# Vectr_1_3.net
KiCad netlist of a schematic drawn in EAGLE
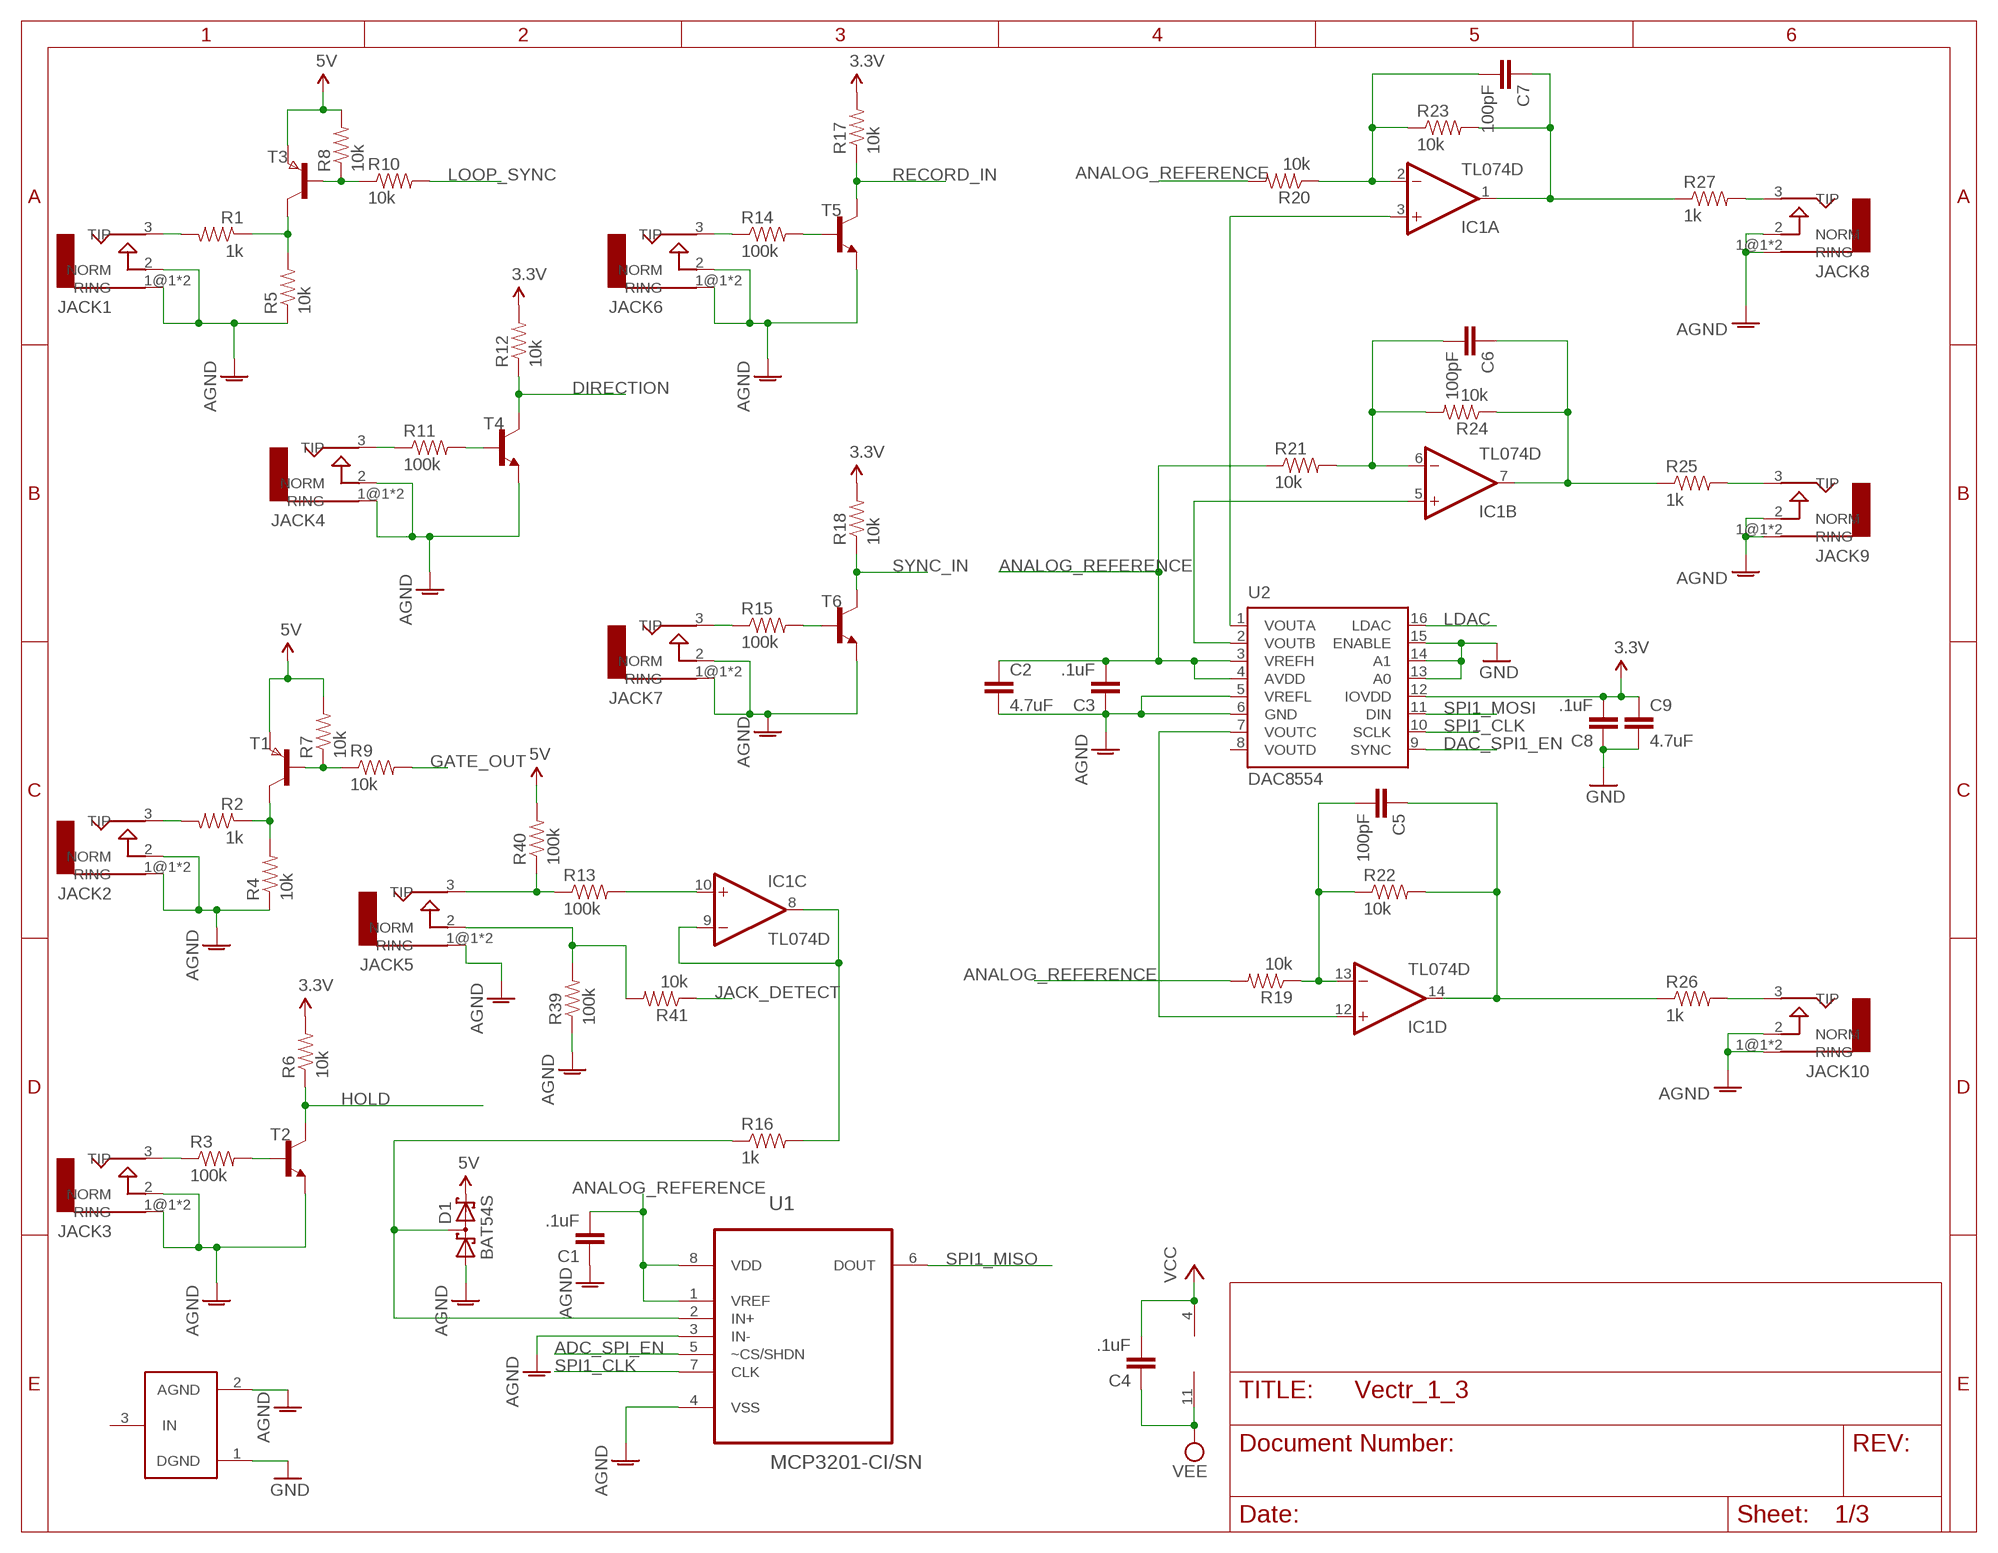
[diagram p0: schematic, sheet 1]
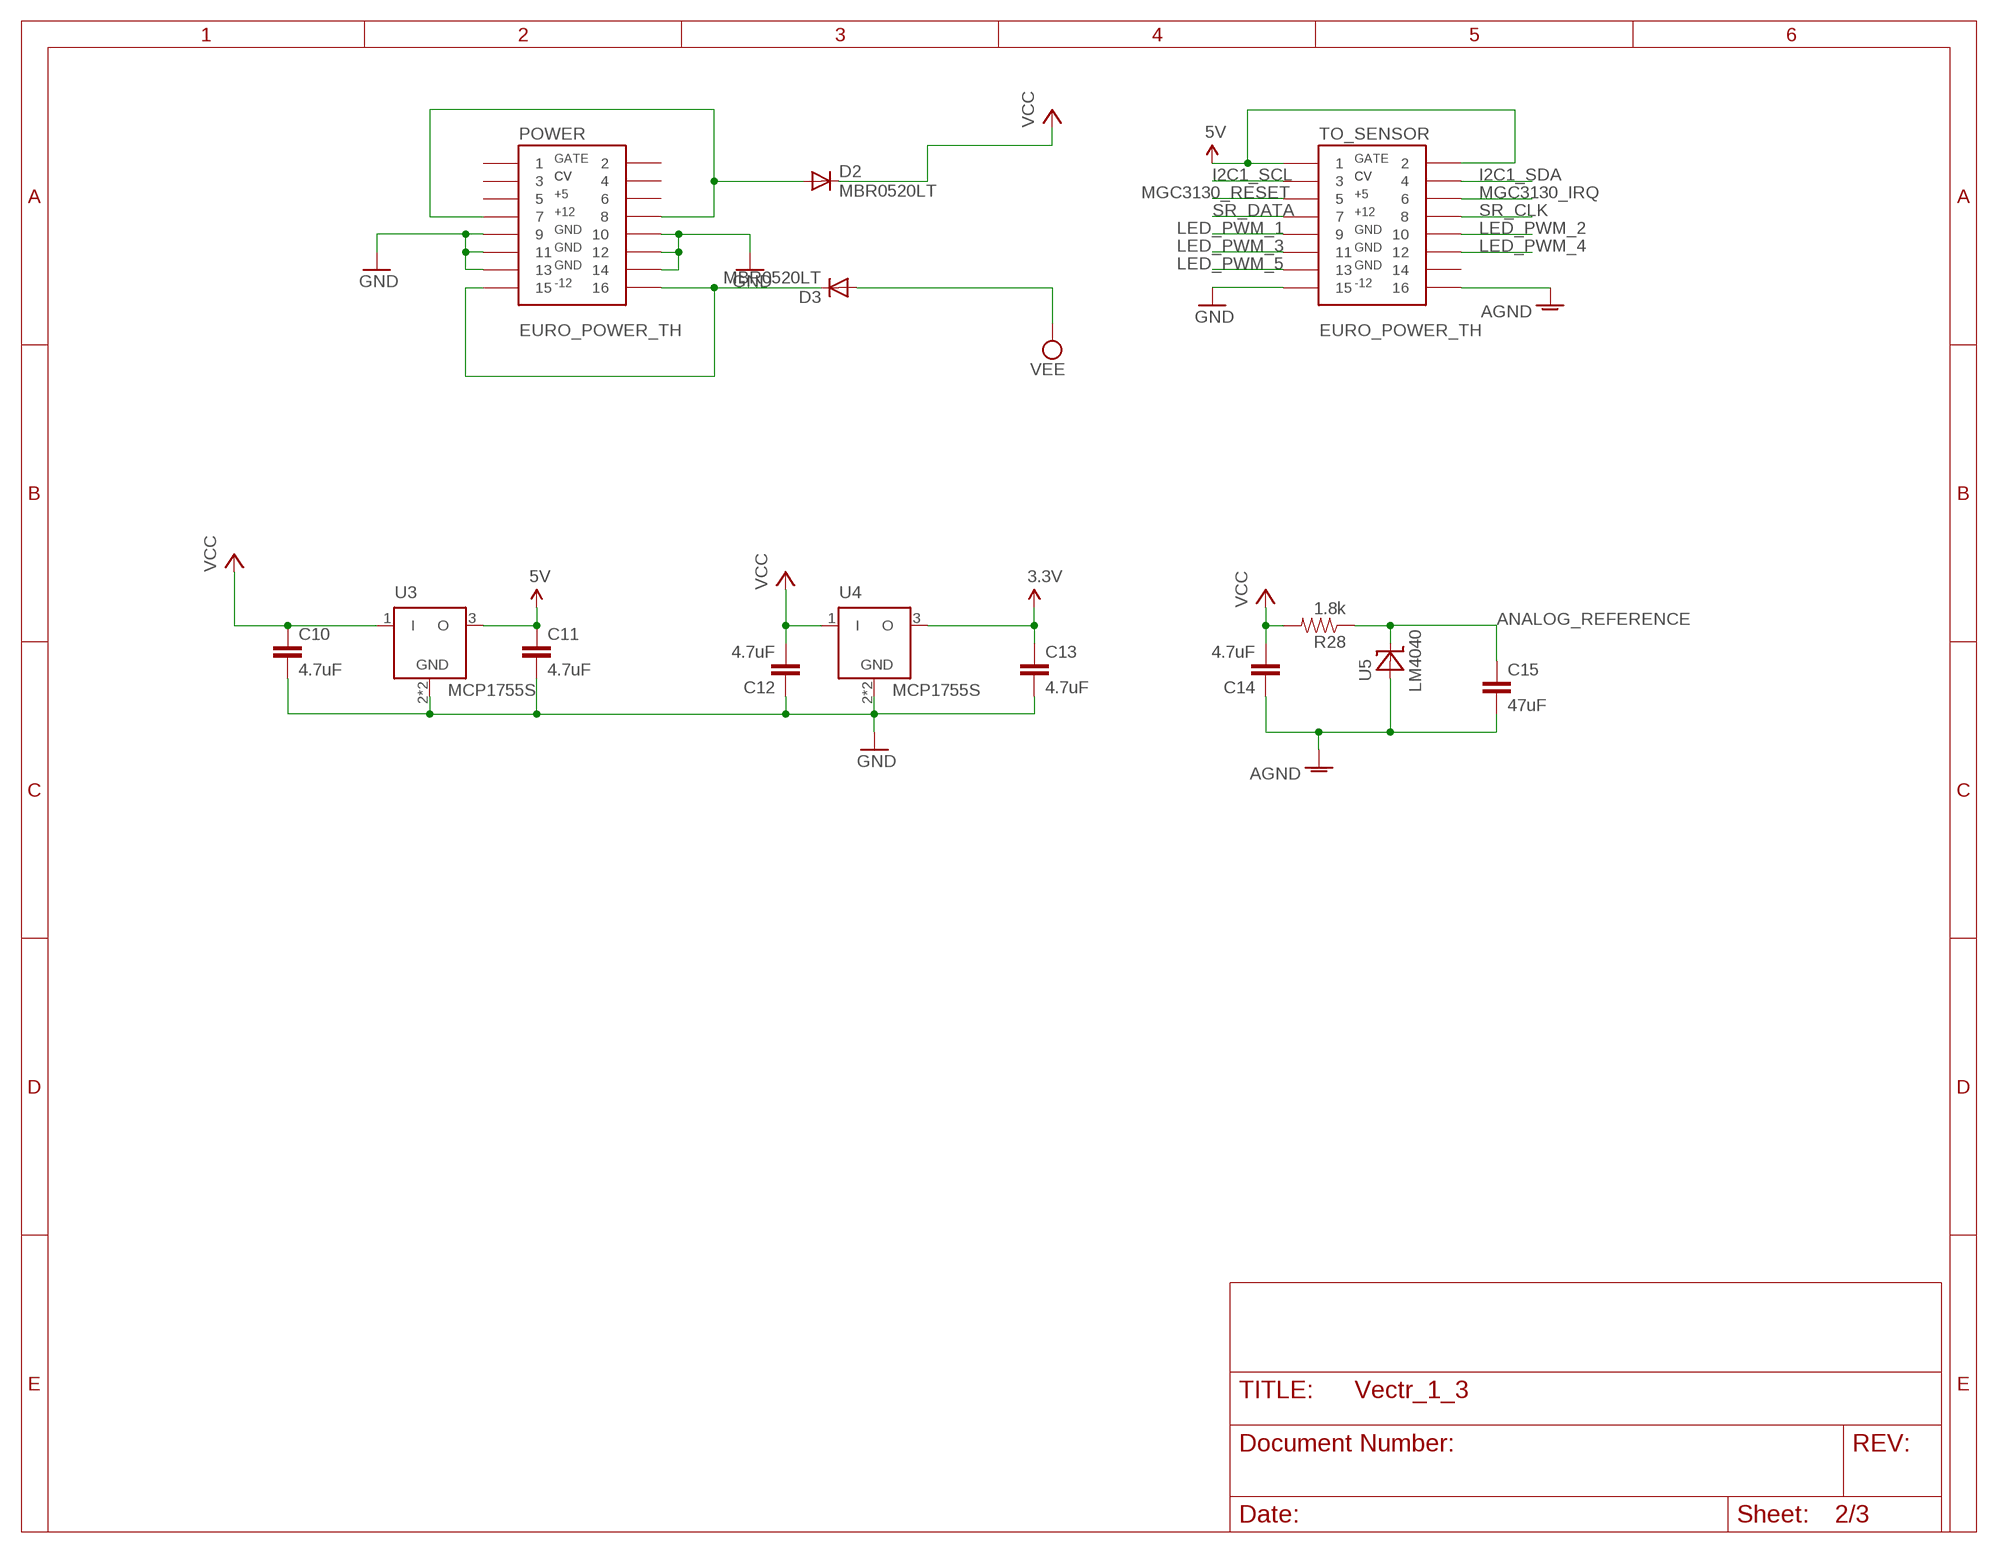
[diagram p1: schematic, sheet 2]
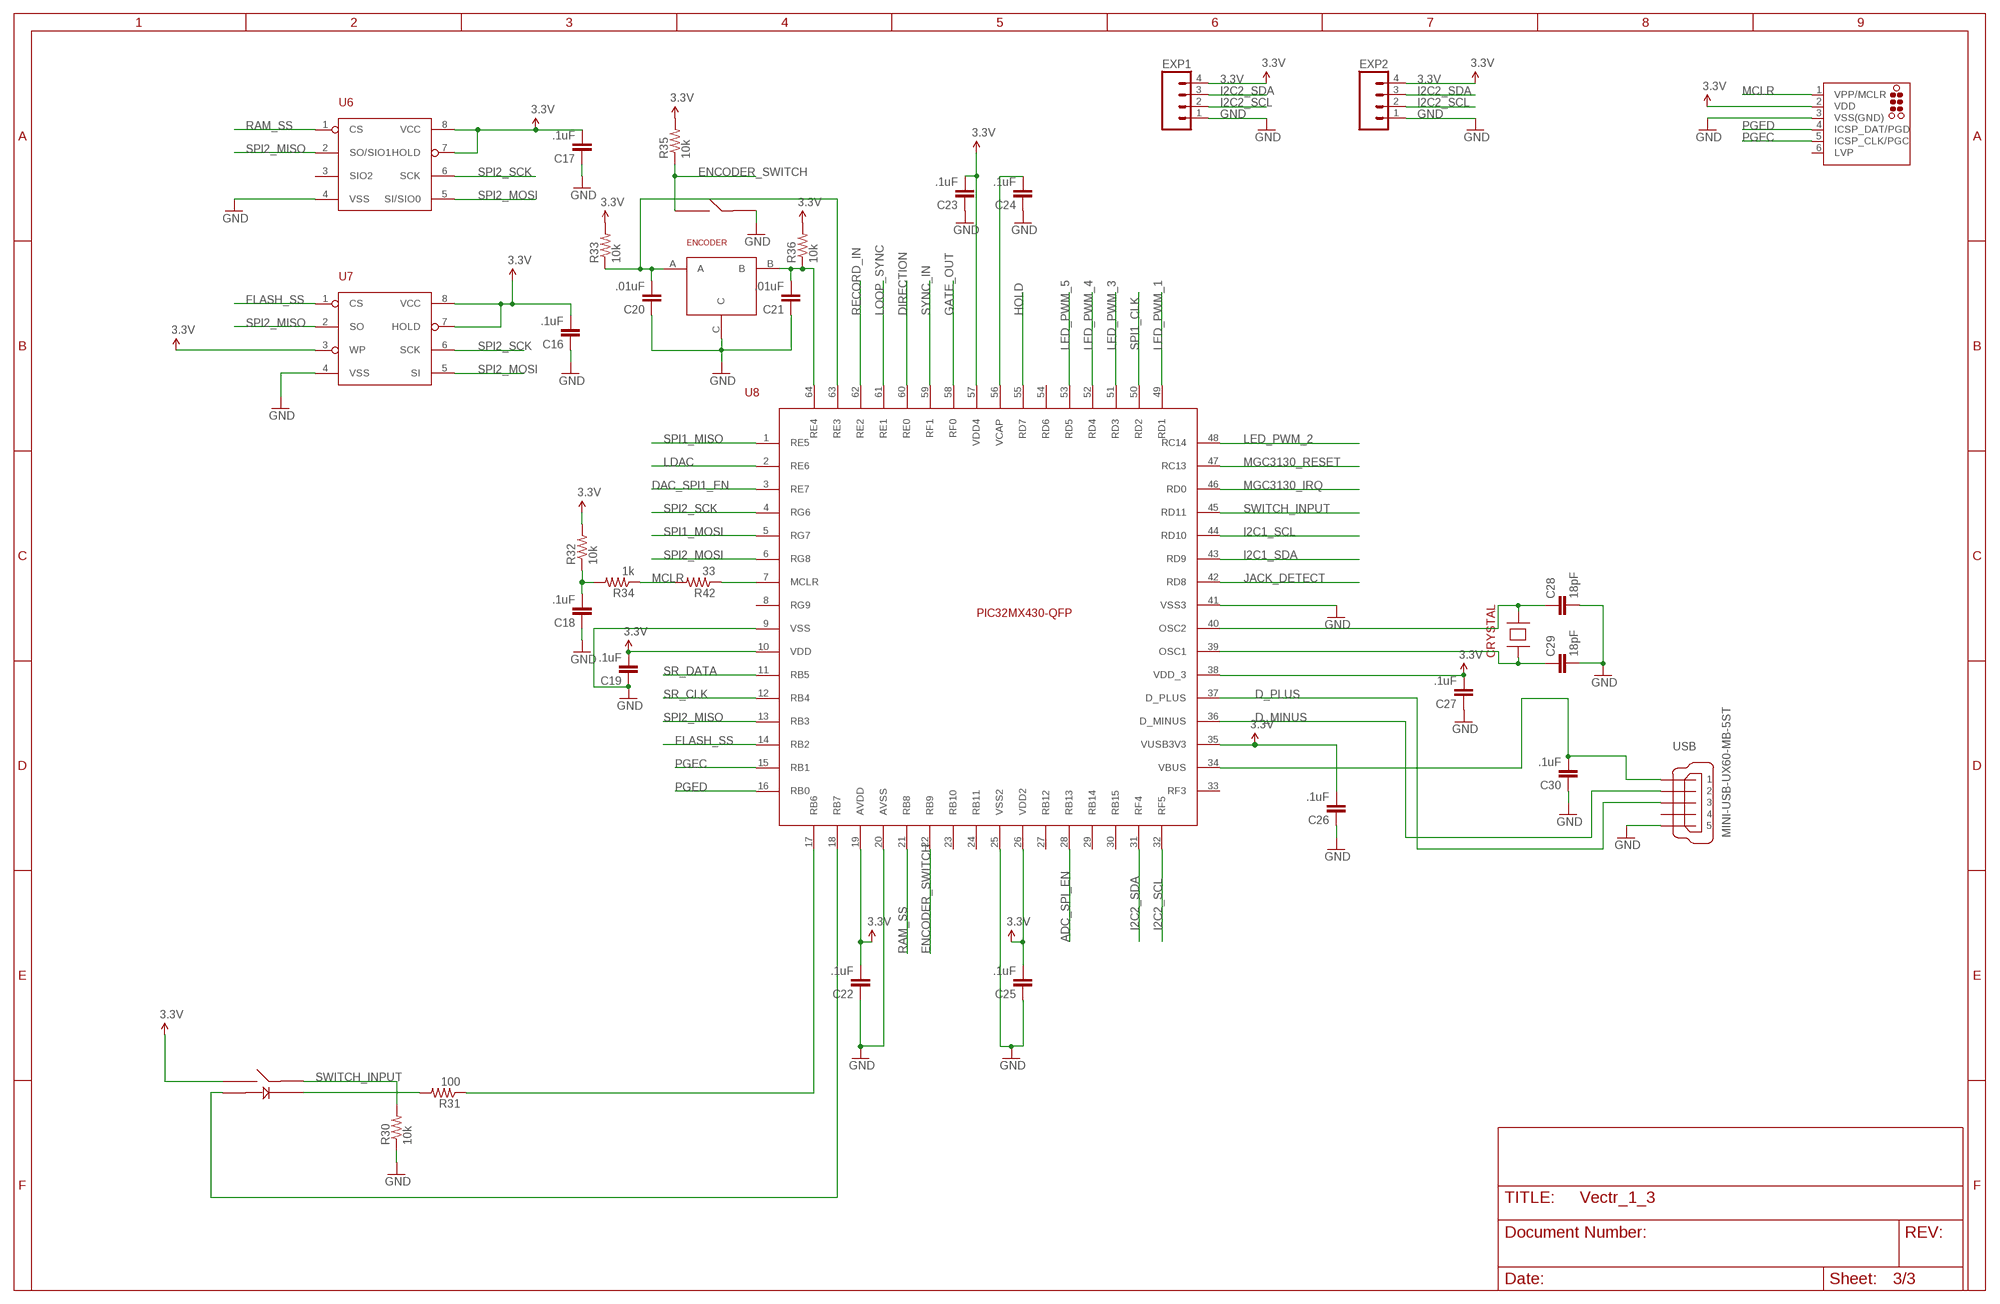
[diagram p2: schematic, sheet 3]

(export (version "E")
  (design (tool "Eeschema 10.0.6"))
  (components
    (comp (ref "C1")
      (value ".1uF")
      (footprint "eagle-import:0402-CAP")
      (libsource (lib "eagle-import") (part "SparkFun-Passives_CAP0402-CAP"))
    )
    (comp (ref "C2")
      (value "4.7uF")
      (footprint "eagle-import:0805")
      (libsource (lib "eagle-import") (part "CAP0805"))
    )
    (comp (ref "C3")
      (value ".1uF")
      (footprint "eagle-import:0402-CAP")
      (libsource (lib "eagle-import") (part "SparkFun-Passives_CAP0402-CAP"))
    )
    (comp (ref "C4")
      (value ".1uF")
      (footprint "eagle-import:0402-CAP")
      (libsource (lib "eagle-import") (part "SparkFun-Passives_CAP0402-CAP"))
    )
    (comp (ref "C5")
      (value "100pF")
      (footprint "eagle-import:0402-CAP")
      (libsource (lib "eagle-import") (part "SparkFun-Passives_CAP0402-CAP"))
    )
    (comp (ref "C6")
      (value "100pF")
      (footprint "eagle-import:0402-CAP")
      (libsource (lib "eagle-import") (part "SparkFun-Passives_CAP0402-CAP"))
    )
    (comp (ref "C7")
      (value "100pF")
      (footprint "eagle-import:0402-CAP")
      (libsource (lib "eagle-import") (part "SparkFun-Passives_CAP0402-CAP"))
    )
    (comp (ref "C8")
      (value ".1uF")
      (footprint "eagle-import:0402-CAP")
      (libsource (lib "eagle-import") (part "SparkFun-Passives_CAP0402-CAP"))
    )
    (comp (ref "C9")
      (value "4.7uF")
      (footprint "eagle-import:0805")
      (libsource (lib "eagle-import") (part "CAP0805"))
    )
    (comp (ref "D1")
      (value "BAT54S")
      (footprint "eagle-import:SOT23")
      (libsource (lib "eagle-import") (part "BAT54S"))
    )
    (comp (ref "GND_CONNECT")
      (value "GND_CONNECT")
      (footprint "eagle-import:GND_CONNECT")
      (libsource (lib "eagle-import") (part "GND_CONNECT"))
    )
    (comp (ref "IC1")
      (value "TL074D")
      (footprint "eagle-import:SO14")
      (libsource (lib "eagle-import") (part "TL074D"))
    )
    (comp (ref "JACK1")
      (value "AUDIO-JACKERTHENVAR")
      (footprint "eagle-import:ERTHENVAR-JACK")
      (libsource (lib "eagle-import") (part "AUDIO-JACKERTHENVAR"))
    )
    (comp (ref "JACK2")
      (value "AUDIO-JACKERTHENVAR")
      (footprint "eagle-import:ERTHENVAR-JACK")
      (libsource (lib "eagle-import") (part "AUDIO-JACKERTHENVAR"))
    )
    (comp (ref "JACK3")
      (value "AUDIO-JACKERTHENVAR")
      (footprint "eagle-import:ERTHENVAR-JACK")
      (libsource (lib "eagle-import") (part "AUDIO-JACKERTHENVAR"))
    )
    (comp (ref "JACK4")
      (value "AUDIO-JACKERTHENVAR")
      (footprint "eagle-import:ERTHENVAR-JACK")
      (libsource (lib "eagle-import") (part "AUDIO-JACKERTHENVAR"))
    )
    (comp (ref "JACK5")
      (value "AUDIO-JACKERTHENVAR")
      (footprint "eagle-import:ERTHENVAR-JACK")
      (libsource (lib "eagle-import") (part "AUDIO-JACKERTHENVAR"))
    )
    (comp (ref "JACK6")
      (value "AUDIO-JACKERTHENVAR")
      (footprint "eagle-import:ERTHENVAR-JACK")
      (libsource (lib "eagle-import") (part "AUDIO-JACKERTHENVAR"))
    )
    (comp (ref "JACK7")
      (value "AUDIO-JACKERTHENVAR")
      (footprint "eagle-import:ERTHENVAR-JACK")
      (libsource (lib "eagle-import") (part "AUDIO-JACKERTHENVAR"))
    )
    (comp (ref "JACK8")
      (value "AUDIO-JACKERTHENVAR")
      (footprint "eagle-import:ERTHENVAR-JACK")
      (libsource (lib "eagle-import") (part "AUDIO-JACKERTHENVAR"))
    )
    (comp (ref "JACK9")
      (value "AUDIO-JACKERTHENVAR")
      (footprint "eagle-import:ERTHENVAR-JACK")
      (libsource (lib "eagle-import") (part "AUDIO-JACKERTHENVAR"))
    )
    (comp (ref "JACK10")
      (value "AUDIO-JACKERTHENVAR")
      (footprint "eagle-import:ERTHENVAR-JACK")
      (libsource (lib "eagle-import") (part "AUDIO-JACKERTHENVAR"))
    )
    (comp (ref "R1")
      (value "1k")
      (footprint "eagle-import:0402-RES")
      (libsource (lib "eagle-import") (part "RESISTOR0402-RES"))
    )
    (comp (ref "R2")
      (value "1k")
      (footprint "eagle-import:0402-RES")
      (libsource (lib "eagle-import") (part "RESISTOR0402-RES"))
    )
    (comp (ref "R3")
      (value "100k")
      (footprint "eagle-import:0402-RES")
      (libsource (lib "eagle-import") (part "RESISTOR0402-RES"))
    )
    (comp (ref "R4")
      (value "10k")
      (footprint "eagle-import:0402-RES")
      (libsource (lib "eagle-import") (part "RESISTOR0402-RES"))
    )
    (comp (ref "R5")
      (value "10k")
      (footprint "eagle-import:0402-RES")
      (libsource (lib "eagle-import") (part "RESISTOR0402-RES"))
    )
    (comp (ref "R6")
      (value "10k")
      (footprint "eagle-import:0402-RES")
      (libsource (lib "eagle-import") (part "RESISTOR0402-RES"))
    )
    (comp (ref "R7")
      (value "10k")
      (footprint "eagle-import:0402-RES")
      (libsource (lib "eagle-import") (part "RESISTOR0402-RES"))
    )
    (comp (ref "R8")
      (value "10k")
      (footprint "eagle-import:0402-RES")
      (libsource (lib "eagle-import") (part "RESISTOR0402-RES"))
    )
    (comp (ref "R9")
      (value "10k")
      (footprint "eagle-import:0402-RES")
      (libsource (lib "eagle-import") (part "RESISTOR0402-RES"))
    )
    (comp (ref "R10")
      (value "10k")
      (footprint "eagle-import:0402-RES")
      (libsource (lib "eagle-import") (part "RESISTOR0402-RES"))
    )
    (comp (ref "R11")
      (value "100k")
      (footprint "eagle-import:0402-RES")
      (libsource (lib "eagle-import") (part "RESISTOR0402-RES"))
    )
    (comp (ref "R12")
      (value "10k")
      (footprint "eagle-import:0402-RES")
      (libsource (lib "eagle-import") (part "RESISTOR0402-RES"))
    )
    (comp (ref "R13")
      (value "100k")
      (footprint "eagle-import:0402-RES")
      (libsource (lib "eagle-import") (part "RESISTOR0402-RES"))
    )
    (comp (ref "R14")
      (value "100k")
      (footprint "eagle-import:0402-RES")
      (libsource (lib "eagle-import") (part "RESISTOR0402-RES"))
    )
    (comp (ref "R15")
      (value "100k")
      (footprint "eagle-import:0402-RES")
      (libsource (lib "eagle-import") (part "RESISTOR0402-RES"))
    )
    (comp (ref "R16")
      (value "1k")
      (footprint "eagle-import:0402-RES")
      (libsource (lib "eagle-import") (part "RESISTOR0402-RES"))
    )
    (comp (ref "R17")
      (value "10k")
      (footprint "eagle-import:0402-RES")
      (libsource (lib "eagle-import") (part "RESISTOR0402-RES"))
    )
    (comp (ref "R18")
      (value "10k")
      (footprint "eagle-import:0402-RES")
      (libsource (lib "eagle-import") (part "RESISTOR0402-RES"))
    )
    (comp (ref "R19")
      (value "10k")
      (footprint "eagle-import:0402-RES")
      (libsource (lib "eagle-import") (part "RESISTOR0402-RES"))
    )
    (comp (ref "R20")
      (value "10k")
      (footprint "eagle-import:0402-RES")
      (libsource (lib "eagle-import") (part "RESISTOR0402-RES"))
    )
    (comp (ref "R21")
      (value "10k")
      (footprint "eagle-import:0402-RES")
      (libsource (lib "eagle-import") (part "RESISTOR0402-RES"))
    )
    (comp (ref "R22")
      (value "10k")
      (footprint "eagle-import:0402-RES")
      (libsource (lib "eagle-import") (part "RESISTOR0402-RES"))
    )
    (comp (ref "R23")
      (value "10k")
      (footprint "eagle-import:0402-RES")
      (libsource (lib "eagle-import") (part "RESISTOR0402-RES"))
    )
    (comp (ref "R24")
      (value "10k")
      (footprint "eagle-import:0402-RES")
      (libsource (lib "eagle-import") (part "RESISTOR0402-RES"))
    )
    (comp (ref "R25")
      (value "1k")
      (footprint "eagle-import:0402-RES")
      (libsource (lib "eagle-import") (part "RESISTOR0402-RES"))
    )
    (comp (ref "R26")
      (value "1k")
      (footprint "eagle-import:0402-RES")
      (libsource (lib "eagle-import") (part "RESISTOR0402-RES"))
    )
    (comp (ref "R27")
      (value "1k")
      (footprint "eagle-import:0402-RES")
      (libsource (lib "eagle-import") (part "RESISTOR0402-RES"))
    )
    (comp (ref "R39")
      (value "100k")
      (footprint "eagle-import:0402-RES")
      (libsource (lib "eagle-import") (part "RESISTOR0402-RES"))
    )
    (comp (ref "R40")
      (value "100k")
      (footprint "eagle-import:0402-RES")
      (libsource (lib "eagle-import") (part "RESISTOR0402-RES"))
    )
    (comp (ref "R41")
      (value "10k")
      (footprint "eagle-import:0402-RES")
      (libsource (lib "eagle-import") (part "RESISTOR0402-RES"))
    )
    (comp (ref "T1")
      (value "PNPSOT23")
      (footprint "eagle-import:SOT-23")
      (fields (field (name "MPN") "DSS20200L-7"))
      (libsource (lib "eagle-import") (part "PNPSOT23"))
    )
    (comp (ref "T2")
      (value "TRANSISTOR_NPNSOT23")
      (footprint "eagle-import:SOT23")
      (libsource (lib "eagle-import") (part "TRANSISTOR_NPNSOT23"))
    )
    (comp (ref "T3")
      (value "PNPSOT23")
      (footprint "eagle-import:SOT-23")
      (fields (field (name "MPN") "DSS20200L-7"))
      (libsource (lib "eagle-import") (part "PNPSOT23"))
    )
    (comp (ref "T4")
      (value "TRANSISTOR_NPNSOT23")
      (footprint "eagle-import:SOT23")
      (libsource (lib "eagle-import") (part "TRANSISTOR_NPNSOT23"))
    )
    (comp (ref "T5")
      (value "TRANSISTOR_NPNSOT23")
      (footprint "eagle-import:SOT23")
      (libsource (lib "eagle-import") (part "TRANSISTOR_NPNSOT23"))
    )
    (comp (ref "T6")
      (value "TRANSISTOR_NPNSOT23")
      (footprint "eagle-import:SOT23")
      (libsource (lib "eagle-import") (part "TRANSISTOR_NPNSOT23"))
    )
    (comp (ref "U1")
      (value "MCP3201-CI/SN")
      (footprint "eagle-import:SOIC127P600X175-8N")
      (libsource (lib "eagle-import") (part "MCP3201-CI/SN"))
    )
    (comp (ref "U2")
      (value "DAC8554")
      (footprint "eagle-import:PW_R-PDSO-G16")
      (libsource (lib "eagle-import") (part "DAC8554"))
    )
    (comp (ref "C10")
      (value "4.7uF")
      (footprint "eagle-import:0805")
      (libsource (lib "eagle-import") (part "CAP0805"))
    )
    (comp (ref "C11")
      (value "4.7uF")
      (footprint "eagle-import:0805")
      (libsource (lib "eagle-import") (part "CAP0805"))
    )
    (comp (ref "C12")
      (value "4.7uF")
      (footprint "eagle-import:0805")
      (libsource (lib "eagle-import") (part "SparkFun-Passives_CAP0805"))
    )
    (comp (ref "C13")
      (value "4.7uF")
      (footprint "eagle-import:0805")
      (libsource (lib "eagle-import") (part "CAP0805"))
    )
    (comp (ref "C14")
      (value "4.7uF")
      (footprint "eagle-import:0805")
      (libsource (lib "eagle-import") (part "SparkFun-Passives_CAP0805"))
    )
    (comp (ref "C15")
      (value "47uF")
      (footprint "eagle-import:0805")
      (libsource (lib "eagle-import") (part "CAP0805"))
    )
    (comp (ref "D2")
      (value "MBR0520LT")
      (footprint "eagle-import:SOD123")
      (libsource (lib "eagle-import") (part "MBR0520LT"))
    )
    (comp (ref "D3")
      (value "MBR0520LT")
      (footprint "eagle-import:SOD123")
      (libsource (lib "eagle-import") (part "MBR0520LT"))
    )
    (comp (ref "POWER")
      (value "EURO_POWER_TH")
      (footprint "eagle-import:EURO_POWER_TH")
      (libsource (lib "eagle-import") (part "EURO_POWER_TH"))
    )
    (comp (ref "R28")
      (value "1.8k")
      (footprint "eagle-import:0402-RES")
      (libsource (lib "eagle-import") (part "RESISTOR0402-RES"))
    )
    (comp (ref "TO_SENSOR")
      (value "EURO_POWER_TH")
      (footprint "eagle-import:EURO_POWER_TH")
      (libsource (lib "eagle-import") (part "EURO_POWER_TH"))
    )
    (comp (ref "U3")
      (value "MCP1755S")
      (footprint "eagle-import:SOT223")
      (libsource (lib "eagle-import") (part "MCP1755S"))
    )
    (comp (ref "U4")
      (value "MCP1755S")
      (footprint "eagle-import:SOT223")
      (libsource (lib "eagle-import") (part "MCP1755S"))
    )
    (comp (ref "U5")
      (value "LM4040")
      (footprint "eagle-import:SOT23")
      (libsource (lib "eagle-import") (part "LM4040"))
    )
    (comp (ref "C16")
      (value ".1uF")
      (footprint "eagle-import:0402-CAP")
      (libsource (lib "eagle-import") (part "SparkFun-Passives_CAP0402-CAP"))
    )
    (comp (ref "C17")
      (value ".1uF")
      (footprint "eagle-import:0402-CAP")
      (libsource (lib "eagle-import") (part "SparkFun-Passives_CAP0402-CAP"))
    )
    (comp (ref "C18")
      (value ".1uF")
      (footprint "eagle-import:0402-CAP")
      (libsource (lib "eagle-import") (part "SparkFun-Passives_CAP0402-CAP"))
    )
    (comp (ref "C19")
      (value ".1uF")
      (footprint "eagle-import:0402-CAP")
      (libsource (lib "eagle-import") (part "SparkFun-Passives_CAP0402-CAP"))
    )
    (comp (ref "C20")
      (value ".01uF")
      (footprint "eagle-import:0402-CAP")
      (libsource (lib "eagle-import") (part "SparkFun-Passives_CAP0402-CAP"))
    )
    (comp (ref "C21")
      (value ".01uF")
      (footprint "eagle-import:0402-CAP")
      (libsource (lib "eagle-import") (part "SparkFun-Passives_CAP0402-CAP"))
    )
    (comp (ref "C22")
      (value ".1uF")
      (footprint "eagle-import:0402-CAP")
      (libsource (lib "eagle-import") (part "SparkFun-Passives_CAP0402-CAP"))
    )
    (comp (ref "C23")
      (value ".1uF")
      (footprint "eagle-import:0402-CAP")
      (libsource (lib "eagle-import") (part "SparkFun-Passives_CAP0402-CAP"))
    )
    (comp (ref "C24")
      (value ".1uF")
      (footprint "eagle-import:0402-CAP")
      (libsource (lib "eagle-import") (part "SparkFun-Passives_CAP0402-CAP"))
    )
    (comp (ref "C25")
      (value ".1uF")
      (footprint "eagle-import:0402-CAP")
      (libsource (lib "eagle-import") (part "SparkFun-Passives_CAP0402-CAP"))
    )
    (comp (ref "C26")
      (value ".1uF")
      (footprint "eagle-import:0402-CAP")
      (libsource (lib "eagle-import") (part "SparkFun-Passives_CAP0402-CAP"))
    )
    (comp (ref "C27")
      (value ".1uF")
      (footprint "eagle-import:0402-CAP")
      (libsource (lib "eagle-import") (part "SparkFun-Passives_CAP0402-CAP"))
    )
    (comp (ref "C28")
      (value "18pF")
      (footprint "eagle-import:0402-CAP")
      (libsource (lib "eagle-import") (part "SparkFun-Passives_CAP0402-CAP"))
    )
    (comp (ref "C29")
      (value "18pF")
      (footprint "eagle-import:0402-CAP")
      (libsource (lib "eagle-import") (part "SparkFun-Passives_CAP0402-CAP"))
    )
    (comp (ref "C30")
      (value ".1uF")
      (footprint "eagle-import:0402-CAP")
      (libsource (lib "eagle-import") (part "SparkFun-Passives_CAP0402-CAP"))
    )
    (comp (ref "CRYSTAL")
      (value "SMD-4-CRYSTAL")
      (footprint "eagle-import:SMD-4-CRYSTAL")
      (libsource (lib "eagle-import") (part "SMD-4-CRYSTAL"))
    )
    (comp (ref "ENCODER")
      (value "PEC16_ENCODER")
      (footprint "eagle-import:PEC16_ENCODER")
      (libsource (lib "eagle-import") (part "PEC16_ENCODER"))
    )
    (comp (ref "EXP1")
      (value "M04PTH")
      (footprint "eagle-import:1X04")
      (libsource (lib "eagle-import") (part "M04PTH"))
    )
    (comp (ref "EXP2")
      (value "M04PTH")
      (footprint "eagle-import:1X04")
      (libsource (lib "eagle-import") (part "M04PTH"))
    )
    (comp (ref "J1")
      (value "TC2030-MCP")
      (footprint "eagle-import:TC2030-MCP")
      (libsource (lib "eagle-import") (part "TC2030-MCP"))
    )
    (comp (ref "R30")
      (value "10k")
      (footprint "eagle-import:0402-RES")
      (libsource (lib "eagle-import") (part "RESISTOR0402-RES"))
    )
    (comp (ref "R31")
      (value "100")
      (footprint "eagle-import:0402-RES")
      (libsource (lib "eagle-import") (part "RESISTOR0402-RES"))
    )
    (comp (ref "R32")
      (value "10k")
      (footprint "eagle-import:0402-RES")
      (libsource (lib "eagle-import") (part "RESISTOR0402-RES"))
    )
    (comp (ref "R33")
      (value "10k")
      (footprint "eagle-import:0402-RES")
      (libsource (lib "eagle-import") (part "RESISTOR0402-RES"))
    )
    (comp (ref "R34")
      (value "1k")
      (footprint "eagle-import:0402-RES")
      (libsource (lib "eagle-import") (part "RESISTOR0402-RES"))
    )
    (comp (ref "R35")
      (value "10k")
      (footprint "eagle-import:0402-RES")
      (libsource (lib "eagle-import") (part "RESISTOR0402-RES"))
    )
    (comp (ref "R36")
      (value "10k")
      (footprint "eagle-import:0402-RES")
      (libsource (lib "eagle-import") (part "RESISTOR0402-RES"))
    )
    (comp (ref "R42")
      (value "33")
      (footprint "eagle-import:0402-RES")
      (libsource (lib "eagle-import") (part "RESISTOR0402-RES"))
    )
    (comp (ref "SWITCH")
      (value "5GSH9")
      (footprint "eagle-import:5GSH9")
      (libsource (lib "eagle-import") (part "5GSH9"))
    )
    (comp (ref "U6")
      (value "23LC512")
      (footprint "eagle-import:SO-08")
      (libsource (lib "eagle-import") (part "23LC512"))
    )
    (comp (ref "U7")
      (value "SST25VF010A")
      (footprint "eagle-import:SO-08")
      (libsource (lib "eagle-import") (part "SST25VF010A"))
    )
    (comp (ref "U8")
      (value "PIC32MX430-QFP")
      (footprint "eagle-import:QFP50P1200X1200X120-64N")
      (libsource (lib "eagle-import") (part "PIC32MX430-QFP"))
    )
    (comp (ref "USB")
      (value "MINI-USB-UX60-MB-5ST")
      (footprint "eagle-import:UX60-MB-5ST")
      (libsource (lib "eagle-import") (part "MINI-USB-UX60-MB-5ST"))
    )
  )
  (nets
    (net (code "1") (name "3.3V") (class "Default")
      (node (ref "C13") (pin "1") (pinfunction "1_1") (pintype "passive"))
      (node (ref "C16") (pin "2") (pinfunction "2_2") (pintype "passive"))
      (node (ref "C17") (pin "2") (pinfunction "2_2") (pintype "passive"))
      (node (ref "C19") (pin "2") (pinfunction "2_2") (pintype "passive"))
      (node (ref "C22") (pin "2") (pinfunction "2_2") (pintype "passive"))
      (node (ref "C23") (pin "2") (pinfunction "2_2") (pintype "passive"))
      (node (ref "C25") (pin "2") (pinfunction "2_2") (pintype "passive"))
      (node (ref "C26") (pin "2") (pinfunction "2_2") (pintype "passive"))
      (node (ref "C27") (pin "2") (pinfunction "2_2") (pintype "passive"))
      (node (ref "C8") (pin "2") (pinfunction "2_2") (pintype "passive"))
      (node (ref "C9") (pin "1") (pinfunction "1_1") (pintype "passive"))
      (node (ref "EXP1") (pin "4") (pinfunction "4_4") (pintype "passive"))
      (node (ref "EXP2") (pin "4") (pinfunction "4_4") (pintype "passive"))
      (node (ref "J1") (pin "2") (pinfunction "VDD_2") (pintype "power_in"))
      (node (ref "R12") (pin "2") (pinfunction "2_2") (pintype "passive"))
      (node (ref "R17") (pin "2") (pinfunction "2_2") (pintype "passive"))
      (node (ref "R18") (pin "2") (pinfunction "2_2") (pintype "passive"))
      (node (ref "R32") (pin "2") (pinfunction "2_2") (pintype "passive"))
      (node (ref "R33") (pin "2") (pinfunction "2_2") (pintype "passive"))
      (node (ref "R35") (pin "2") (pinfunction "2_2") (pintype "passive"))
      (node (ref "R36") (pin "2") (pinfunction "2_2") (pintype "passive"))
      (node (ref "R6") (pin "2") (pinfunction "2_2") (pintype "passive"))
      (node (ref "SWITCH") (pin "1") (pinfunction "1_1") (pintype "bidirectional"))
      (node (ref "U2") (pin "12") (pinfunction "IOVDD_12") (pintype "input"))
      (node (ref "U4") (pin "3") (pinfunction "O_3") (pintype "input"))
      (node (ref "U6") (pin "7") (pinfunction "HOLD_7") (pintype "bidirectional"))
      (node (ref "U6") (pin "8") (pinfunction "VCC_8") (pintype "power_in"))
      (node (ref "U7") (pin "3") (pinfunction "WP_3") (pintype "bidirectional"))
      (node (ref "U7") (pin "7") (pinfunction "HOLD_7") (pintype "bidirectional"))
      (node (ref "U7") (pin "8") (pinfunction "VCC_8") (pintype "power_in"))
      (node (ref "U8") (pin "10") (pinfunction "VDD_10") (pintype "bidirectional"))
      (node (ref "U8") (pin "19") (pinfunction "AVDD_19") (pintype "bidirectional"))
      (node (ref "U8") (pin "26") (pinfunction "VDD2_26") (pintype "bidirectional"))
      (node (ref "U8") (pin "35") (pinfunction "VUSB3V3_35") (pintype "bidirectional"))
      (node (ref "U8") (pin "38") (pinfunction "VDD_3_38") (pintype "bidirectional"))
      (node (ref "U8") (pin "57") (pinfunction "VDD4_57") (pintype "bidirectional"))
    )
    (net (code "2") (name "5V") (class "Default")
      (node (ref "C11") (pin "1") (pinfunction "1_1") (pintype "passive"))
      (node (ref "D1") (pin "2") (pinfunction "C2_2") (pintype "passive"))
      (node (ref "R40") (pin "2") (pinfunction "2_2") (pintype "passive"))
      (node (ref "R7") (pin "2") (pinfunction "2_2") (pintype "passive"))
      (node (ref "R8") (pin "2") (pinfunction "2_2") (pintype "passive"))
      (node (ref "T1") (pin "2") (pinfunction "E_2") (pintype "passive"))
      (node (ref "T3") (pin "2") (pinfunction "E_2") (pintype "passive"))
      (node (ref "TO_SENSOR") (pin "1") (pinfunction "1_1") (pintype "bidirectional"))
      (node (ref "TO_SENSOR") (pin "2") (pinfunction "2_2") (pintype "bidirectional"))
      (node (ref "U3") (pin "3") (pinfunction "O_3") (pintype "input"))
    )
    (net (code "3") (name "ADC_SPI_EN") (class "Default")
      (node (ref "U1") (pin "5") (pinfunction "~{CS/SHDN}_5") (pintype "input"))
      (node (ref "U8") (pin "28") (pinfunction "RB13_28") (pintype "bidirectional"))
    )
    (net (code "4") (name "AGND") (class "Default")
      (node (ref "C1") (pin "1") (pinfunction "1_1") (pintype "passive"))
      (node (ref "C14") (pin "1") (pinfunction "1_1") (pintype "passive"))
      (node (ref "C15") (pin "2") (pinfunction "2_2") (pintype "passive"))
      (node (ref "C2") (pin "2") (pinfunction "2_2") (pintype "passive"))
      (node (ref "C3") (pin "1") (pinfunction "1_1") (pintype "passive"))
      (node (ref "D1") (pin "1") (pinfunction "A1_1") (pintype "passive"))
      (node (ref "GND_CONNECT") (pin "2") (pinfunction "AGND_2") (pintype "bidirectional"))
      (node (ref "JACK1") (pin "1@1") (pinfunction "RING_1@1") (pintype "bidirectional"))
      (node (ref "JACK1") (pin "1@2") (pinfunction "RING_1@2") (pintype "bidirectional"))
      (node (ref "JACK1") (pin "2") (pinfunction "NORM_2") (pintype "bidirectional"))
      (node (ref "JACK10") (pin "1@1") (pinfunction "RING_1@1") (pintype "bidirectional"))
      (node (ref "JACK10") (pin "1@2") (pinfunction "RING_1@2") (pintype "bidirectional"))
      (node (ref "JACK10") (pin "2") (pinfunction "NORM_2") (pintype "bidirectional"))
      (node (ref "JACK2") (pin "1@1") (pinfunction "RING_1@1") (pintype "bidirectional"))
      (node (ref "JACK2") (pin "1@2") (pinfunction "RING_1@2") (pintype "bidirectional"))
      (node (ref "JACK2") (pin "2") (pinfunction "NORM_2") (pintype "bidirectional"))
      (node (ref "JACK3") (pin "1@1") (pinfunction "RING_1@1") (pintype "bidirectional"))
      (node (ref "JACK3") (pin "1@2") (pinfunction "RING_1@2") (pintype "bidirectional"))
      (node (ref "JACK3") (pin "2") (pinfunction "NORM_2") (pintype "bidirectional"))
      (node (ref "JACK4") (pin "1@1") (pinfunction "RING_1@1") (pintype "bidirectional"))
      (node (ref "JACK4") (pin "1@2") (pinfunction "RING_1@2") (pintype "bidirectional"))
      (node (ref "JACK4") (pin "2") (pinfunction "NORM_2") (pintype "bidirectional"))
      (node (ref "JACK5") (pin "1@1") (pinfunction "RING_1@1") (pintype "bidirectional"))
      (node (ref "JACK5") (pin "1@2") (pinfunction "RING_1@2") (pintype "bidirectional"))
      (node (ref "JACK6") (pin "1@1") (pinfunction "RING_1@1") (pintype "bidirectional"))
      (node (ref "JACK6") (pin "1@2") (pinfunction "RING_1@2") (pintype "bidirectional"))
      (node (ref "JACK6") (pin "2") (pinfunction "NORM_2") (pintype "bidirectional"))
      (node (ref "JACK7") (pin "1@1") (pinfunction "RING_1@1") (pintype "bidirectional"))
      (node (ref "JACK7") (pin "1@2") (pinfunction "RING_1@2") (pintype "bidirectional"))
      (node (ref "JACK7") (pin "2") (pinfunction "NORM_2") (pintype "bidirectional"))
      (node (ref "JACK8") (pin "1@1") (pinfunction "RING_1@1") (pintype "bidirectional"))
      (node (ref "JACK8") (pin "1@2") (pinfunction "RING_1@2") (pintype "bidirectional"))
      (node (ref "JACK8") (pin "2") (pinfunction "NORM_2") (pintype "bidirectional"))
      (node (ref "JACK9") (pin "1@1") (pinfunction "RING_1@1") (pintype "bidirectional"))
      (node (ref "JACK9") (pin "1@2") (pinfunction "RING_1@2") (pintype "bidirectional"))
      (node (ref "JACK9") (pin "2") (pinfunction "NORM_2") (pintype "bidirectional"))
      (node (ref "R39") (pin "1") (pinfunction "1_1") (pintype "passive"))
      (node (ref "R4") (pin "1") (pinfunction "1_1") (pintype "passive"))
      (node (ref "R5") (pin "1") (pinfunction "1_1") (pintype "passive"))
      (node (ref "T2") (pin "2") (pinfunction "E_2") (pintype "passive"))
      (node (ref "T4") (pin "2") (pinfunction "E_2") (pintype "passive"))
      (node (ref "T5") (pin "2") (pinfunction "E_2") (pintype "passive"))
      (node (ref "T6") (pin "2") (pinfunction "E_2") (pintype "passive"))
      (node (ref "TO_SENSOR") (pin "16") (pinfunction "16_16") (pintype "bidirectional"))
      (node (ref "U1") (pin "3") (pinfunction "IN-_3") (pintype "input"))
      (node (ref "U1") (pin "4") (pinfunction "VSS_4") (pintype "power_in"))
      (node (ref "U2") (pin "5") (pinfunction "VREFL_5") (pintype "input"))
      (node (ref "U2") (pin "6") (pinfunction "GND_6") (pintype "input"))
      (node (ref "U5") (pin "2") (pinfunction "A_2") (pintype "passive"))
    )
    (net (code "5") (name "ANALOG_REFERENCE") (class "Default")
      (node (ref "C1") (pin "2") (pinfunction "2_2") (pintype "passive"))
      (node (ref "C15") (pin "1") (pinfunction "1_1") (pintype "passive"))
      (node (ref "C2") (pin "1") (pinfunction "1_1") (pintype "passive"))
      (node (ref "C3") (pin "2") (pinfunction "2_2") (pintype "passive"))
      (node (ref "R19") (pin "2") (pinfunction "2_2") (pintype "passive"))
      (node (ref "R20") (pin "2") (pinfunction "2_2") (pintype "passive"))
      (node (ref "R21") (pin "1") (pinfunction "1_1") (pintype "passive"))
      (node (ref "R28") (pin "1") (pinfunction "1_1") (pintype "passive"))
      (node (ref "U1") (pin "1") (pinfunction "VREF_1") (pintype "input"))
      (node (ref "U1") (pin "8") (pinfunction "VDD_8") (pintype "power_in"))
      (node (ref "U2") (pin "3") (pinfunction "VREFH_3") (pintype "input"))
      (node (ref "U2") (pin "4") (pinfunction "AVDD_4") (pintype "input"))
      (node (ref "U5") (pin "3") (pinfunction "C_3") (pintype "passive"))
    )
    (net (code "6") (name "DAC_SPI1_EN") (class "Default")
      (node (ref "U2") (pin "9") (pinfunction "SYNC_9") (pintype "input"))
      (node (ref "U8") (pin "3") (pinfunction "RE7_3") (pintype "bidirectional"))
    )
    (net (code "7") (name "DIRECTION") (class "Default")
      (node (ref "R12") (pin "1") (pinfunction "1_1") (pintype "passive"))
      (node (ref "T4") (pin "3") (pinfunction "C_3") (pintype "passive"))
      (node (ref "U8") (pin "60") (pinfunction "RE0_60") (pintype "bidirectional"))
    )
    (net (code "8") (name "D_MINUS") (class "Default")
      (node (ref "U8") (pin "36") (pinfunction "D_MINUS_36") (pintype "bidirectional"))
      (node (ref "USB") (pin "2") (pinfunction "2_2") (pintype "input"))
    )
    (net (code "9") (name "D_PLUS") (class "Default")
      (node (ref "U8") (pin "37") (pinfunction "D_PLUS_37") (pintype "bidirectional"))
      (node (ref "USB") (pin "3") (pinfunction "3_3") (pintype "input"))
    )
    (net (code "10") (name "ENCODER_SWITCH") (class "Default")
      (node (ref "ENCODER") (pin "D") (pinfunction "D_D") (pintype "bidirectional"))
      (node (ref "R35") (pin "1") (pinfunction "1_1") (pintype "passive"))
      (node (ref "U8") (pin "22") (pinfunction "RB9_22") (pintype "bidirectional"))
    )
    (net (code "11") (name "FLASH_SS") (class "Default")
      (node (ref "U7") (pin "1") (pinfunction "CS_1") (pintype "bidirectional"))
      (node (ref "U8") (pin "14") (pinfunction "RB2_14") (pintype "bidirectional"))
    )
    (net (code "12") (name "GATE_OUT") (class "Default")
      (node (ref "R9") (pin "2") (pinfunction "2_2") (pintype "passive"))
      (node (ref "U8") (pin "58") (pinfunction "RF0_58") (pintype "bidirectional"))
    )
    (net (code "13") (name "GND") (class "Default")
      (node (ref "C10") (pin "2") (pinfunction "2_2") (pintype "passive"))
      (node (ref "C11") (pin "2") (pinfunction "2_2") (pintype "passive"))
      (node (ref "C12") (pin "1") (pinfunction "1_1") (pintype "passive"))
      (node (ref "C13") (pin "2") (pinfunction "2_2") (pintype "passive"))
      (node (ref "C16") (pin "1") (pinfunction "1_1") (pintype "passive"))
      (node (ref "C17") (pin "1") (pinfunction "1_1") (pintype "passive"))
      (node (ref "C18") (pin "1") (pinfunction "1_1") (pintype "passive"))
      (node (ref "C19") (pin "1") (pinfunction "1_1") (pintype "passive"))
      (node (ref "C20") (pin "1") (pinfunction "1_1") (pintype "passive"))
      (node (ref "C21") (pin "1") (pinfunction "1_1") (pintype "passive"))
      (node (ref "C22") (pin "1") (pinfunction "1_1") (pintype "passive"))
      (node (ref "C23") (pin "1") (pinfunction "1_1") (pintype "passive"))
      (node (ref "C24") (pin "1") (pinfunction "1_1") (pintype "passive"))
      (node (ref "C25") (pin "1") (pinfunction "1_1") (pintype "passive"))
      (node (ref "C26") (pin "1") (pinfunction "1_1") (pintype "passive"))
      (node (ref "C27") (pin "1") (pinfunction "1_1") (pintype "passive"))
      (node (ref "C28") (pin "2") (pinfunction "2_2") (pintype "passive"))
      (node (ref "C29") (pin "2") (pinfunction "2_2") (pintype "passive"))
      (node (ref "C30") (pin "1") (pinfunction "1_1") (pintype "passive"))
      (node (ref "C8") (pin "1") (pinfunction "1_1") (pintype "passive"))
      (node (ref "C9") (pin "2") (pinfunction "2_2") (pintype "passive"))
      (node (ref "ENCODER") (pin "C") (pinfunction "C_C") (pintype "bidirectional"))
      (node (ref "ENCODER") (pin "E") (pinfunction "E_E") (pintype "bidirectional"))
      (node (ref "EXP1") (pin "1") (pinfunction "1_1") (pintype "passive"))
      (node (ref "EXP2") (pin "1") (pinfunction "1_1") (pintype "passive"))
      (node (ref "GND_CONNECT") (pin "1") (pinfunction "DGND_1") (pintype "bidirectional"))
      (node (ref "J1") (pin "3") (pinfunction "VSS(GND)_3") (pintype "power_in"))
      (node (ref "POWER") (pin "10") (pinfunction "10_10") (pintype "bidirectional"))
      (node (ref "POWER") (pin "11") (pinfunction "11_11") (pintype "bidirectional"))
      (node (ref "POWER") (pin "12") (pinfunction "12_12") (pintype "bidirectional"))
      (node (ref "POWER") (pin "13") (pinfunction "13_13") (pintype "bidirectional"))
      (node (ref "POWER") (pin "14") (pinfunction "14_14") (pintype "bidirectional"))
      (node (ref "POWER") (pin "9") (pinfunction "9_9") (pintype "bidirectional"))
      (node (ref "R30") (pin "1") (pinfunction "1_1") (pintype "passive"))
      (node (ref "TO_SENSOR") (pin "15") (pinfunction "15_15") (pintype "bidirectional"))
      (node (ref "U2") (pin "13") (pinfunction "A0_13") (pintype "input"))
      (node (ref "U2") (pin "14") (pinfunction "A1_14") (pintype "input"))
      (node (ref "U2") (pin "15") (pinfunction "ENABLE_15") (pintype "input"))
      (node (ref "U3") (pin "2") (pinfunction "GND_2") (pintype "power_in"))
      (node (ref "U3") (pin "4") (pinfunction "GND_4") (pintype "power_in"))
      (node (ref "U4") (pin "2") (pinfunction "GND_2") (pintype "power_in"))
      (node (ref "U4") (pin "4") (pinfunction "GND_4") (pintype "power_in"))
      (node (ref "U6") (pin "4") (pinfunction "VSS_4") (pintype "power_in"))
      (node (ref "U7") (pin "4") (pinfunction "VSS_4") (pintype "power_in"))
      (node (ref "U8") (pin "20") (pinfunction "AVSS_20") (pintype "bidirectional"))
      (node (ref "U8") (pin "25") (pinfunction "VSS2_25") (pintype "bidirectional"))
      (node (ref "U8") (pin "41") (pinfunction "VSS3_41") (pintype "bidirectional"))
      (node (ref "U8") (pin "9") (pinfunction "VSS_9") (pintype "bidirectional"))
      (node (ref "USB") (pin "5") (pinfunction "5_5") (pintype "input"))
    )
    (net (code "14") (name "HOLD") (class "Default")
      (node (ref "R6") (pin "1") (pinfunction "1_1") (pintype "passive"))
      (node (ref "T2") (pin "3") (pinfunction "C_3") (pintype "passive"))
      (node (ref "U8") (pin "55") (pinfunction "RD7_55") (pintype "bidirectional"))
    )
    (net (code "15") (name "I2C1_SCL") (class "Default")
      (node (ref "TO_SENSOR") (pin "3") (pinfunction "3_3") (pintype "bidirectional"))
      (node (ref "U8") (pin "44") (pinfunction "RD10_44") (pintype "bidirectional"))
    )
    (net (code "16") (name "I2C1_SDA") (class "Default")
      (node (ref "TO_SENSOR") (pin "4") (pinfunction "4_4") (pintype "bidirectional"))
      (node (ref "U8") (pin "43") (pinfunction "RD9_43") (pintype "bidirectional"))
    )
    (net (code "17") (name "I2C2_SCL") (class "Default")
      (node (ref "EXP1") (pin "2") (pinfunction "2_2") (pintype "passive"))
      (node (ref "EXP2") (pin "2") (pinfunction "2_2") (pintype "passive"))
      (node (ref "U8") (pin "32") (pinfunction "RF5_32") (pintype "bidirectional"))
    )
    (net (code "18") (name "I2C2_SDA") (class "Default")
      (node (ref "EXP1") (pin "3") (pinfunction "3_3") (pintype "passive"))
      (node (ref "EXP2") (pin "3") (pinfunction "3_3") (pintype "passive"))
      (node (ref "U8") (pin "31") (pinfunction "RF4_31") (pintype "bidirectional"))
    )
    (net (code "19") (name "JACK_DETECT") (class "Default")
      (node (ref "R41") (pin "1") (pinfunction "1_1") (pintype "passive"))
      (node (ref "U8") (pin "42") (pinfunction "RD8_42") (pintype "bidirectional"))
    )
    (net (code "20") (name "LDAC") (class "Default")
      (node (ref "U2") (pin "16") (pinfunction "LDAC_16") (pintype "input"))
      (node (ref "U8") (pin "2") (pinfunction "RE6_2") (pintype "bidirectional"))
    )
    (net (code "21") (name "LED_PWM_1") (class "Default")
      (node (ref "TO_SENSOR") (pin "9") (pinfunction "9_9") (pintype "bidirectional"))
      (node (ref "U8") (pin "49") (pinfunction "RD1_49") (pintype "bidirectional"))
    )
    (net (code "22") (name "LED_PWM_2") (class "Default")
      (node (ref "TO_SENSOR") (pin "10") (pinfunction "10_10") (pintype "bidirectional"))
      (node (ref "U8") (pin "48") (pinfunction "RC14_48") (pintype "bidirectional"))
    )
    (net (code "23") (name "LED_PWM_3") (class "Default")
      (node (ref "TO_SENSOR") (pin "11") (pinfunction "11_11") (pintype "bidirectional"))
      (node (ref "U8") (pin "51") (pinfunction "RD3_51") (pintype "bidirectional"))
    )
    (net (code "24") (name "LED_PWM_4") (class "Default")
      (node (ref "TO_SENSOR") (pin "12") (pinfunction "12_12") (pintype "bidirectional"))
      (node (ref "U8") (pin "52") (pinfunction "RD4_52") (pintype "bidirectional"))
    )
    (net (code "25") (name "LED_PWM_5") (class "Default")
      (node (ref "TO_SENSOR") (pin "13") (pinfunction "13_13") (pintype "bidirectional"))
      (node (ref "U8") (pin "53") (pinfunction "RD5_53") (pintype "bidirectional"))
    )
    (net (code "26") (name "LOOP_SYNC") (class "Default")
      (node (ref "R10") (pin "2") (pinfunction "2_2") (pintype "passive"))
      (node (ref "U8") (pin "61") (pinfunction "RE1_61") (pintype "bidirectional"))
    )
    (net (code "27") (name "MCLR") (class "Default")
      (node (ref "J1") (pin "1") (pinfunction "VPP/MCLR_1") (pintype "passive"))
      (node (ref "R34") (pin "1") (pinfunction "1_1") (pintype "passive"))
      (node (ref "R42") (pin "2") (pinfunction "2_2") (pintype "passive"))
    )
    (net (code "28") (name "MGC3130_IRQ") (class "Default")
      (node (ref "TO_SENSOR") (pin "6") (pinfunction "6_6") (pintype "bidirectional"))
      (node (ref "U8") (pin "46") (pinfunction "RD0_46") (pintype "bidirectional"))
    )
    (net (code "29") (name "MGC3130_RESET") (class "Default")
      (node (ref "TO_SENSOR") (pin "5") (pinfunction "5_5") (pintype "bidirectional"))
      (node (ref "U8") (pin "47") (pinfunction "RC13_47") (pintype "bidirectional"))
    )
    (net (code "30") (name "Net-(C18-Pad2)") (class "Default")
      (node (ref "C18") (pin "2") (pinfunction "2_2") (pintype "passive"))
      (node (ref "R32") (pin "1") (pinfunction "1_1") (pintype "passive"))
      (node (ref "R34") (pin "2") (pinfunction "2_2") (pintype "passive"))
    )
    (net (code "31") (name "Net-(D1-C1A2)") (class "Default")
      (node (ref "D1") (pin "3") (pinfunction "C1A2_3") (pintype "passive"))
      (node (ref "R16") (pin "1") (pinfunction "1_1") (pintype "passive"))
      (node (ref "U1") (pin "2") (pinfunction "IN+_2") (pintype "input"))
    )
    (net (code "32") (name "Net-(D2-PadA)") (class "Default")
      (node (ref "D2") (pin "A") (pinfunction "A_A") (pintype "passive"))
      (node (ref "POWER") (pin "7") (pinfunction "7_7") (pintype "bidirectional"))
      (node (ref "POWER") (pin "8") (pinfunction "8_8") (pintype "bidirectional"))
    )
    (net (code "33") (name "Net-(D3-PadC)") (class "Default")
      (node (ref "D3") (pin "C") (pinfunction "C_C") (pintype "passive"))
      (node (ref "POWER") (pin "15") (pinfunction "15_15") (pintype "bidirectional"))
      (node (ref "POWER") (pin "16") (pinfunction "16_16") (pintype "bidirectional"))
    )
    (net (code "34") (name "Net-(IC1A-+IN)") (class "Default")
      (node (ref "IC1") (pin "3") (pinfunction "+IN_3") (pintype "input"))
      (node (ref "U2") (pin "1") (pinfunction "VOUTA_1") (pintype "input"))
    )
    (net (code "35") (name "Net-(IC1A--IN)") (class "Default")
      (node (ref "C7") (pin "2") (pinfunction "2_2") (pintype "passive"))
      (node (ref "IC1") (pin "2") (pinfunction "-IN_2") (pintype "input"))
      (node (ref "R20") (pin "1") (pinfunction "1_1") (pintype "passive"))
      (node (ref "R23") (pin "1") (pinfunction "1_1") (pintype "passive"))
    )
    (net (code "36") (name "Net-(IC1A-OUT)") (class "Default")
      (node (ref "C7") (pin "1") (pinfunction "1_1") (pintype "passive"))
      (node (ref "IC1") (pin "1") (pinfunction "OUT_1") (pintype "output"))
      (node (ref "R23") (pin "2") (pinfunction "2_2") (pintype "passive"))
      (node (ref "R27") (pin "1") (pinfunction "1_1") (pintype "passive"))
    )
    (net (code "37") (name "Net-(IC1B-+IN)") (class "Default")
      (node (ref "IC1") (pin "5") (pinfunction "+IN_5") (pintype "input"))
      (node (ref "U2") (pin "2") (pinfunction "VOUTB_2") (pintype "input"))
    )
    (net (code "38") (name "Net-(IC1B--IN)") (class "Default")
      (node (ref "C6") (pin "2") (pinfunction "2_2") (pintype "passive"))
      (node (ref "IC1") (pin "6") (pinfunction "-IN_6") (pintype "input"))
      (node (ref "R21") (pin "2") (pinfunction "2_2") (pintype "passive"))
      (node (ref "R24") (pin "2") (pinfunction "2_2") (pintype "passive"))
    )
    (net (code "39") (name "Net-(IC1B-OUT)") (class "Default")
      (node (ref "C6") (pin "1") (pinfunction "1_1") (pintype "passive"))
      (node (ref "IC1") (pin "7") (pinfunction "OUT_7") (pintype "output"))
      (node (ref "R24") (pin "1") (pinfunction "1_1") (pintype "passive"))
      (node (ref "R25") (pin "1") (pinfunction "1_1") (pintype "passive"))
    )
    (net (code "40") (name "Net-(IC1C-+IN)") (class "Default")
      (node (ref "IC1") (pin "10") (pinfunction "+IN_10") (pintype "input"))
      (node (ref "R13") (pin "2") (pinfunction "2_2") (pintype "passive"))
    )
    (net (code "41") (name "Net-(IC1C--IN)") (class "Default")
      (node (ref "IC1") (pin "8") (pinfunction "OUT_8") (pintype "output"))
      (node (ref "IC1") (pin "9") (pinfunction "-IN_9") (pintype "input"))
      (node (ref "R16") (pin "2") (pinfunction "2_2") (pintype "passive"))
    )
    (net (code "42") (name "Net-(IC1D-+IN)") (class "Default")
      (node (ref "IC1") (pin "12") (pinfunction "+IN_12") (pintype "input"))
      (node (ref "U2") (pin "7") (pinfunction "VOUTC_7") (pintype "input"))
    )
    (net (code "43") (name "Net-(IC1D--IN)") (class "Default")
      (node (ref "C5") (pin "2") (pinfunction "2_2") (pintype "passive"))
      (node (ref "IC1") (pin "13") (pinfunction "-IN_13") (pintype "input"))
      (node (ref "R19") (pin "1") (pinfunction "1_1") (pintype "passive"))
      (node (ref "R22") (pin "1") (pinfunction "1_1") (pintype "passive"))
    )
    (net (code "44") (name "Net-(IC1D-OUT)") (class "Default")
      (node (ref "C5") (pin "1") (pinfunction "1_1") (pintype "passive"))
      (node (ref "IC1") (pin "14") (pinfunction "OUT_14") (pintype "output"))
      (node (ref "R22") (pin "2") (pinfunction "2_2") (pintype "passive"))
      (node (ref "R26") (pin "1") (pinfunction "1_1") (pintype "passive"))
    )
    (net (code "45") (name "Net-(JACK1-TIP)") (class "Default")
      (node (ref "JACK1") (pin "3") (pinfunction "TIP_3") (pintype "bidirectional"))
      (node (ref "R1") (pin "2") (pinfunction "2_2") (pintype "passive"))
    )
    (net (code "46") (name "Net-(JACK2-TIP)") (class "Default")
      (node (ref "JACK2") (pin "3") (pinfunction "TIP_3") (pintype "bidirectional"))
      (node (ref "R2") (pin "2") (pinfunction "2_2") (pintype "passive"))
    )
    (net (code "47") (name "Net-(JACK3-TIP)") (class "Default")
      (node (ref "JACK3") (pin "3") (pinfunction "TIP_3") (pintype "bidirectional"))
      (node (ref "R3") (pin "1") (pinfunction "1_1") (pintype "passive"))
    )
    (net (code "48") (name "Net-(JACK4-TIP)") (class "Default")
      (node (ref "JACK4") (pin "3") (pinfunction "TIP_3") (pintype "bidirectional"))
      (node (ref "R11") (pin "1") (pinfunction "1_1") (pintype "passive"))
    )
    (net (code "49") (name "Net-(JACK5-NORM)") (class "Default")
      (node (ref "JACK5") (pin "2") (pinfunction "NORM_2") (pintype "bidirectional"))
      (node (ref "R39") (pin "2") (pinfunction "2_2") (pintype "passive"))
      (node (ref "R41") (pin "2") (pinfunction "2_2") (pintype "passive"))
    )
    (net (code "50") (name "Net-(JACK5-TIP)") (class "Default")
      (node (ref "JACK5") (pin "3") (pinfunction "TIP_3") (pintype "bidirectional"))
      (node (ref "R13") (pin "1") (pinfunction "1_1") (pintype "passive"))
      (node (ref "R40") (pin "1") (pinfunction "1_1") (pintype "passive"))
    )
    (net (code "51") (name "Net-(JACK6-TIP)") (class "Default")
      (node (ref "JACK6") (pin "3") (pinfunction "TIP_3") (pintype "bidirectional"))
      (node (ref "R14") (pin "1") (pinfunction "1_1") (pintype "passive"))
    )
    (net (code "52") (name "Net-(JACK7-TIP)") (class "Default")
      (node (ref "JACK7") (pin "3") (pinfunction "TIP_3") (pintype "bidirectional"))
      (node (ref "R15") (pin "1") (pinfunction "1_1") (pintype "passive"))
    )
    (net (code "53") (name "Net-(JACK8-TIP)") (class "Default")
      (node (ref "JACK8") (pin "3") (pinfunction "TIP_3") (pintype "bidirectional"))
      (node (ref "R27") (pin "2") (pinfunction "2_2") (pintype "passive"))
    )
    (net (code "54") (name "Net-(JACK9-TIP)") (class "Default")
      (node (ref "JACK9") (pin "3") (pinfunction "TIP_3") (pintype "bidirectional"))
      (node (ref "R25") (pin "2") (pinfunction "2_2") (pintype "passive"))
    )
    (net (code "55") (name "Net-(JACK10-TIP)") (class "Default")
      (node (ref "JACK10") (pin "3") (pinfunction "TIP_3") (pintype "bidirectional"))
      (node (ref "R26") (pin "2") (pinfunction "2_2") (pintype "passive"))
    )
    (net (code "56") (name "Net-(R31-Pad2)") (class "Default")
      (node (ref "R31") (pin "2") (pinfunction "2_2") (pintype "passive"))
      (node (ref "SWITCH") (pin "2") (pinfunction "2_2") (pintype "bidirectional"))
    )
    (net (code "57") (name "Net-(T1-B)") (class "Default")
      (node (ref "R7") (pin "1") (pinfunction "1_1") (pintype "passive"))
      (node (ref "R9") (pin "1") (pinfunction "1_1") (pintype "passive"))
      (node (ref "T1") (pin "3") (pinfunction "B_3") (pintype "passive"))
    )
    (net (code "58") (name "Net-(T1-C)") (class "Default")
      (node (ref "R2") (pin "1") (pinfunction "1_1") (pintype "passive"))
      (node (ref "R4") (pin "2") (pinfunction "2_2") (pintype "passive"))
      (node (ref "T1") (pin "1") (pinfunction "C_1") (pintype "passive"))
    )
    (net (code "59") (name "Net-(T2-B)") (class "Default")
      (node (ref "R3") (pin "2") (pinfunction "2_2") (pintype "passive"))
      (node (ref "T2") (pin "1") (pinfunction "B_1") (pintype "passive"))
    )
    (net (code "60") (name "Net-(T3-B)") (class "Default")
      (node (ref "R10") (pin "1") (pinfunction "1_1") (pintype "passive"))
      (node (ref "R8") (pin "1") (pinfunction "1_1") (pintype "passive"))
      (node (ref "T3") (pin "3") (pinfunction "B_3") (pintype "passive"))
    )
    (net (code "61") (name "Net-(T3-C)") (class "Default")
      (node (ref "R1") (pin "1") (pinfunction "1_1") (pintype "passive"))
      (node (ref "R5") (pin "2") (pinfunction "2_2") (pintype "passive"))
      (node (ref "T3") (pin "1") (pinfunction "C_1") (pintype "passive"))
    )
    (net (code "62") (name "Net-(T4-B)") (class "Default")
      (node (ref "R11") (pin "2") (pinfunction "2_2") (pintype "passive"))
      (node (ref "T4") (pin "1") (pinfunction "B_1") (pintype "passive"))
    )
    (net (code "63") (name "Net-(T5-B)") (class "Default")
      (node (ref "R14") (pin "2") (pinfunction "2_2") (pintype "passive"))
      (node (ref "T5") (pin "1") (pinfunction "B_1") (pintype "passive"))
    )
    (net (code "64") (name "Net-(T6-B)") (class "Default")
      (node (ref "R15") (pin "2") (pinfunction "2_2") (pintype "passive"))
      (node (ref "T6") (pin "1") (pinfunction "B_1") (pintype "passive"))
    )
    (net (code "65") (name "Net-(U8-MCLR)") (class "Default")
      (node (ref "R42") (pin "1") (pinfunction "1_1") (pintype "passive"))
      (node (ref "U8") (pin "7") (pinfunction "MCLR_7") (pintype "bidirectional"))
    )
    (net (code "66") (name "Net-(U8-OSC1)") (class "Default")
      (node (ref "C29") (pin "1") (pinfunction "1_1") (pintype "passive"))
      (node (ref "CRYSTAL") (pin "1") (pinfunction "1_1") (pintype "bidirectional"))
      (node (ref "U8") (pin "39") (pinfunction "OSC1_39") (pintype "bidirectional"))
    )
    (net (code "67") (name "Net-(U8-OSC2)") (class "Default")
      (node (ref "C28") (pin "1") (pinfunction "1_1") (pintype "passive"))
      (node (ref "CRYSTAL") (pin "3") (pinfunction "3_3") (pintype "bidirectional"))
      (node (ref "U8") (pin "40") (pinfunction "OSC2_40") (pintype "bidirectional"))
    )
    (net (code "68") (name "Net-(U8-RB6)") (class "Default")
      (node (ref "R31") (pin "1") (pinfunction "1_1") (pintype "passive"))
      (node (ref "U8") (pin "17") (pinfunction "RB6_17") (pintype "bidirectional"))
    )
    (net (code "69") (name "Net-(U8-RB7)") (class "Default")
      (node (ref "SWITCH") (pin "3") (pinfunction "3_3") (pintype "bidirectional"))
      (node (ref "U8") (pin "18") (pinfunction "RB7_18") (pintype "bidirectional"))
    )
    (net (code "70") (name "Net-(U8-RE3)") (class "Default")
      (node (ref "C20") (pin "2") (pinfunction "2_2") (pintype "passive"))
      (node (ref "ENCODER") (pin "A") (pinfunction "A_A") (pintype "bidirectional"))
      (node (ref "R33") (pin "1") (pinfunction "1_1") (pintype "passive"))
      (node (ref "U8") (pin "63") (pinfunction "RE3_63") (pintype "bidirectional"))
    )
    (net (code "71") (name "Net-(U8-RE4)") (class "Default")
      (node (ref "C21") (pin "2") (pinfunction "2_2") (pintype "passive"))
      (node (ref "ENCODER") (pin "B") (pinfunction "B_B") (pintype "bidirectional"))
      (node (ref "R36") (pin "1") (pinfunction "1_1") (pintype "passive"))
      (node (ref "U8") (pin "64") (pinfunction "RE4_64") (pintype "bidirectional"))
    )
    (net (code "72") (name "Net-(U8-VBUS)") (class "Default")
      (node (ref "C30") (pin "2") (pinfunction "2_2") (pintype "passive"))
      (node (ref "U8") (pin "34") (pinfunction "VBUS_34") (pintype "bidirectional"))
      (node (ref "USB") (pin "1") (pinfunction "1_1") (pintype "input"))
    )
    (net (code "73") (name "Net-(U8-VCAP)") (class "Default")
      (node (ref "C24") (pin "2") (pinfunction "2_2") (pintype "passive"))
      (node (ref "U8") (pin "56") (pinfunction "VCAP_56") (pintype "bidirectional"))
    )
    (net (code "74") (name "PGEC") (class "Default")
      (node (ref "J1") (pin "5") (pinfunction "ICSP_CLK/PGC_5") (pintype "output"))
      (node (ref "U8") (pin "15") (pinfunction "RB1_15") (pintype "bidirectional"))
    )
    (net (code "75") (name "PGED") (class "Default")
      (node (ref "J1") (pin "4") (pinfunction "ICSP_DAT/PGD_4") (pintype "bidirectional"))
      (node (ref "U8") (pin "16") (pinfunction "RB0_16") (pintype "bidirectional"))
    )
    (net (code "76") (name "RAM_SS") (class "Default")
      (node (ref "U6") (pin "1") (pinfunction "CS_1") (pintype "bidirectional"))
      (node (ref "U8") (pin "21") (pinfunction "RB8_21") (pintype "bidirectional"))
    )
    (net (code "77") (name "RECORD_IN") (class "Default")
      (node (ref "R17") (pin "1") (pinfunction "1_1") (pintype "passive"))
      (node (ref "T5") (pin "3") (pinfunction "C_3") (pintype "passive"))
      (node (ref "U8") (pin "62") (pinfunction "RE2_62") (pintype "bidirectional"))
    )
    (net (code "78") (name "SPI1_CLK") (class "Default")
      (node (ref "U1") (pin "7") (pinfunction "CLK_7") (pintype "input"))
      (node (ref "U2") (pin "10") (pinfunction "SCLK_10") (pintype "input"))
      (node (ref "U8") (pin "50") (pinfunction "RD2_50") (pintype "bidirectional"))
    )
    (net (code "79") (name "SPI1_MISO") (class "Default")
      (node (ref "U1") (pin "6") (pinfunction "DOUT_6") (pintype "output"))
      (node (ref "U8") (pin "1") (pinfunction "RE5_1") (pintype "bidirectional"))
    )
    (net (code "80") (name "SPI1_MOSI") (class "Default")
      (node (ref "U2") (pin "11") (pinfunction "DIN_11") (pintype "input"))
      (node (ref "U8") (pin "5") (pinfunction "RG7_5") (pintype "bidirectional"))
    )
    (net (code "81") (name "SPI2_MISO") (class "Default")
      (node (ref "U6") (pin "2") (pinfunction "SO/SIO1_2") (pintype "bidirectional"))
      (node (ref "U7") (pin "2") (pinfunction "SO_2") (pintype "bidirectional"))
      (node (ref "U8") (pin "13") (pinfunction "RB3_13") (pintype "bidirectional"))
    )
    (net (code "82") (name "SPI2_MOSI") (class "Default")
      (node (ref "U6") (pin "5") (pinfunction "SI/SIO0_5") (pintype "bidirectional"))
      (node (ref "U7") (pin "5") (pinfunction "SI_5") (pintype "bidirectional"))
      (node (ref "U8") (pin "6") (pinfunction "RG8_6") (pintype "bidirectional"))
    )
    (net (code "83") (name "SPI2_SCK") (class "Default")
      (node (ref "U6") (pin "6") (pinfunction "SCK_6") (pintype "bidirectional"))
      (node (ref "U7") (pin "6") (pinfunction "SCK_6") (pintype "bidirectional"))
      (node (ref "U8") (pin "4") (pinfunction "RG6_4") (pintype "bidirectional"))
    )
    (net (code "84") (name "SR_CLK") (class "Default")
      (node (ref "TO_SENSOR") (pin "8") (pinfunction "8_8") (pintype "bidirectional"))
      (node (ref "U8") (pin "12") (pinfunction "RB4_12") (pintype "bidirectional"))
    )
    (net (code "85") (name "SR_DATA") (class "Default")
      (node (ref "TO_SENSOR") (pin "7") (pinfunction "7_7") (pintype "bidirectional"))
      (node (ref "U8") (pin "11") (pinfunction "RB5_11") (pintype "bidirectional"))
    )
    (net (code "86") (name "SWITCH_INPUT") (class "Default")
      (node (ref "R30") (pin "2") (pinfunction "2_2") (pintype "passive"))
      (node (ref "SWITCH") (pin "4") (pinfunction "4_4") (pintype "bidirectional"))
      (node (ref "U8") (pin "45") (pinfunction "RD11_45") (pintype "bidirectional"))
    )
    (net (code "87") (name "SYNC_IN") (class "Default")
      (node (ref "R18") (pin "1") (pinfunction "1_1") (pintype "passive"))
      (node (ref "T6") (pin "3") (pinfunction "C_3") (pintype "passive"))
      (node (ref "U8") (pin "59") (pinfunction "RF1_59") (pintype "bidirectional"))
    )
    (net (code "88") (name "VCC") (class "Default")
      (node (ref "C10") (pin "1") (pinfunction "1_1") (pintype "passive"))
      (node (ref "C12") (pin "2") (pinfunction "2_2") (pintype "passive"))
      (node (ref "C14") (pin "2") (pinfunction "2_2") (pintype "passive"))
      (node (ref "C4") (pin "2") (pinfunction "2_2") (pintype "passive"))
      (node (ref "D2") (pin "C") (pinfunction "C_C") (pintype "passive"))
      (node (ref "IC1") (pin "4") (pinfunction "V+_4") (pintype "power_in"))
      (node (ref "R28") (pin "2") (pinfunction "2_2") (pintype "passive"))
      (node (ref "U3") (pin "1") (pinfunction "I_1") (pintype "input"))
      (node (ref "U4") (pin "1") (pinfunction "I_1") (pintype "input"))
    )
    (net (code "89") (name "VEE") (class "Default")
      (node (ref "C4") (pin "1") (pinfunction "1_1") (pintype "passive"))
      (node (ref "D3") (pin "A") (pinfunction "A_A") (pintype "passive"))
      (node (ref "IC1") (pin "11") (pinfunction "V-_11") (pintype "power_in"))
    )
    (net (code "90") (name "unconnected-(GND_CONNECT-IN-Pad3)") (class "Default")
      (node (ref "GND_CONNECT") (pin "3") (pinfunction "IN_3") (pintype "bidirectional"))
    )
    (net (code "91") (name "unconnected-(J1-LVP-Pad6)") (class "Default")
      (node (ref "J1") (pin "6") (pinfunction "LVP_6") (pintype "bidirectional"))
    )
    (net (code "92") (name "unconnected-(POWER-Pad1)") (class "Default")
      (node (ref "POWER") (pin "1") (pinfunction "1_1") (pintype "bidirectional"))
    )
    (net (code "93") (name "unconnected-(POWER-Pad2)") (class "Default")
      (node (ref "POWER") (pin "2") (pinfunction "2_2") (pintype "bidirectional"))
    )
    (net (code "94") (name "unconnected-(POWER-Pad3)") (class "Default")
      (node (ref "POWER") (pin "3") (pinfunction "3_3") (pintype "bidirectional"))
    )
    (net (code "95") (name "unconnected-(POWER-Pad4)") (class "Default")
      (node (ref "POWER") (pin "4") (pinfunction "4_4") (pintype "bidirectional"))
    )
    (net (code "96") (name "unconnected-(POWER-Pad5)") (class "Default")
      (node (ref "POWER") (pin "5") (pinfunction "5_5") (pintype "bidirectional"))
    )
    (net (code "97") (name "unconnected-(POWER-Pad6)") (class "Default")
      (node (ref "POWER") (pin "6") (pinfunction "6_6") (pintype "bidirectional"))
    )
    (net (code "98") (name "unconnected-(TO_SENSOR-Pad14)") (class "Default")
      (node (ref "TO_SENSOR") (pin "14") (pinfunction "14_14") (pintype "bidirectional"))
    )
    (net (code "99") (name "unconnected-(U2-VOUTD-Pad8)") (class "Default")
      (node (ref "U2") (pin "8") (pinfunction "VOUTD_8") (pintype "input"))
    )
    (net (code "100") (name "unconnected-(U6-SIO2-Pad3)") (class "Default")
      (node (ref "U6") (pin "3") (pinfunction "SIO2_3") (pintype "bidirectional"))
    )
    (net (code "101") (name "unconnected-(U8-RB10-Pad23)") (class "Default")
      (node (ref "U8") (pin "23") (pinfunction "RB10_23") (pintype "bidirectional"))
    )
    (net (code "102") (name "unconnected-(U8-RB11-Pad24)") (class "Default")
      (node (ref "U8") (pin "24") (pinfunction "RB11_24") (pintype "bidirectional"))
    )
    (net (code "103") (name "unconnected-(U8-RB12-Pad27)") (class "Default")
      (node (ref "U8") (pin "27") (pinfunction "RB12_27") (pintype "bidirectional"))
    )
    (net (code "104") (name "unconnected-(U8-RB14-Pad29)") (class "Default")
      (node (ref "U8") (pin "29") (pinfunction "RB14_29") (pintype "bidirectional"))
    )
    (net (code "105") (name "unconnected-(U8-RB15-Pad30)") (class "Default")
      (node (ref "U8") (pin "30") (pinfunction "RB15_30") (pintype "bidirectional"))
    )
    (net (code "106") (name "unconnected-(U8-RD6-Pad54)") (class "Default")
      (node (ref "U8") (pin "54") (pinfunction "RD6_54") (pintype "bidirectional"))
    )
    (net (code "107") (name "unconnected-(U8-RF3-Pad33)") (class "Default")
      (node (ref "U8") (pin "33") (pinfunction "RF3_33") (pintype "bidirectional"))
    )
    (net (code "108") (name "unconnected-(U8-RG9-Pad8)") (class "Default")
      (node (ref "U8") (pin "8") (pinfunction "RG9_8") (pintype "bidirectional"))
    )
    (net (code "109") (name "unconnected-(USB-Pad4)") (class "Default")
      (node (ref "USB") (pin "4") (pinfunction "4_4") (pintype "input"))
    )
  )
)
